# IOT_Masterv1.net
KiCad netlist of a schematic drawn in Altium Designer
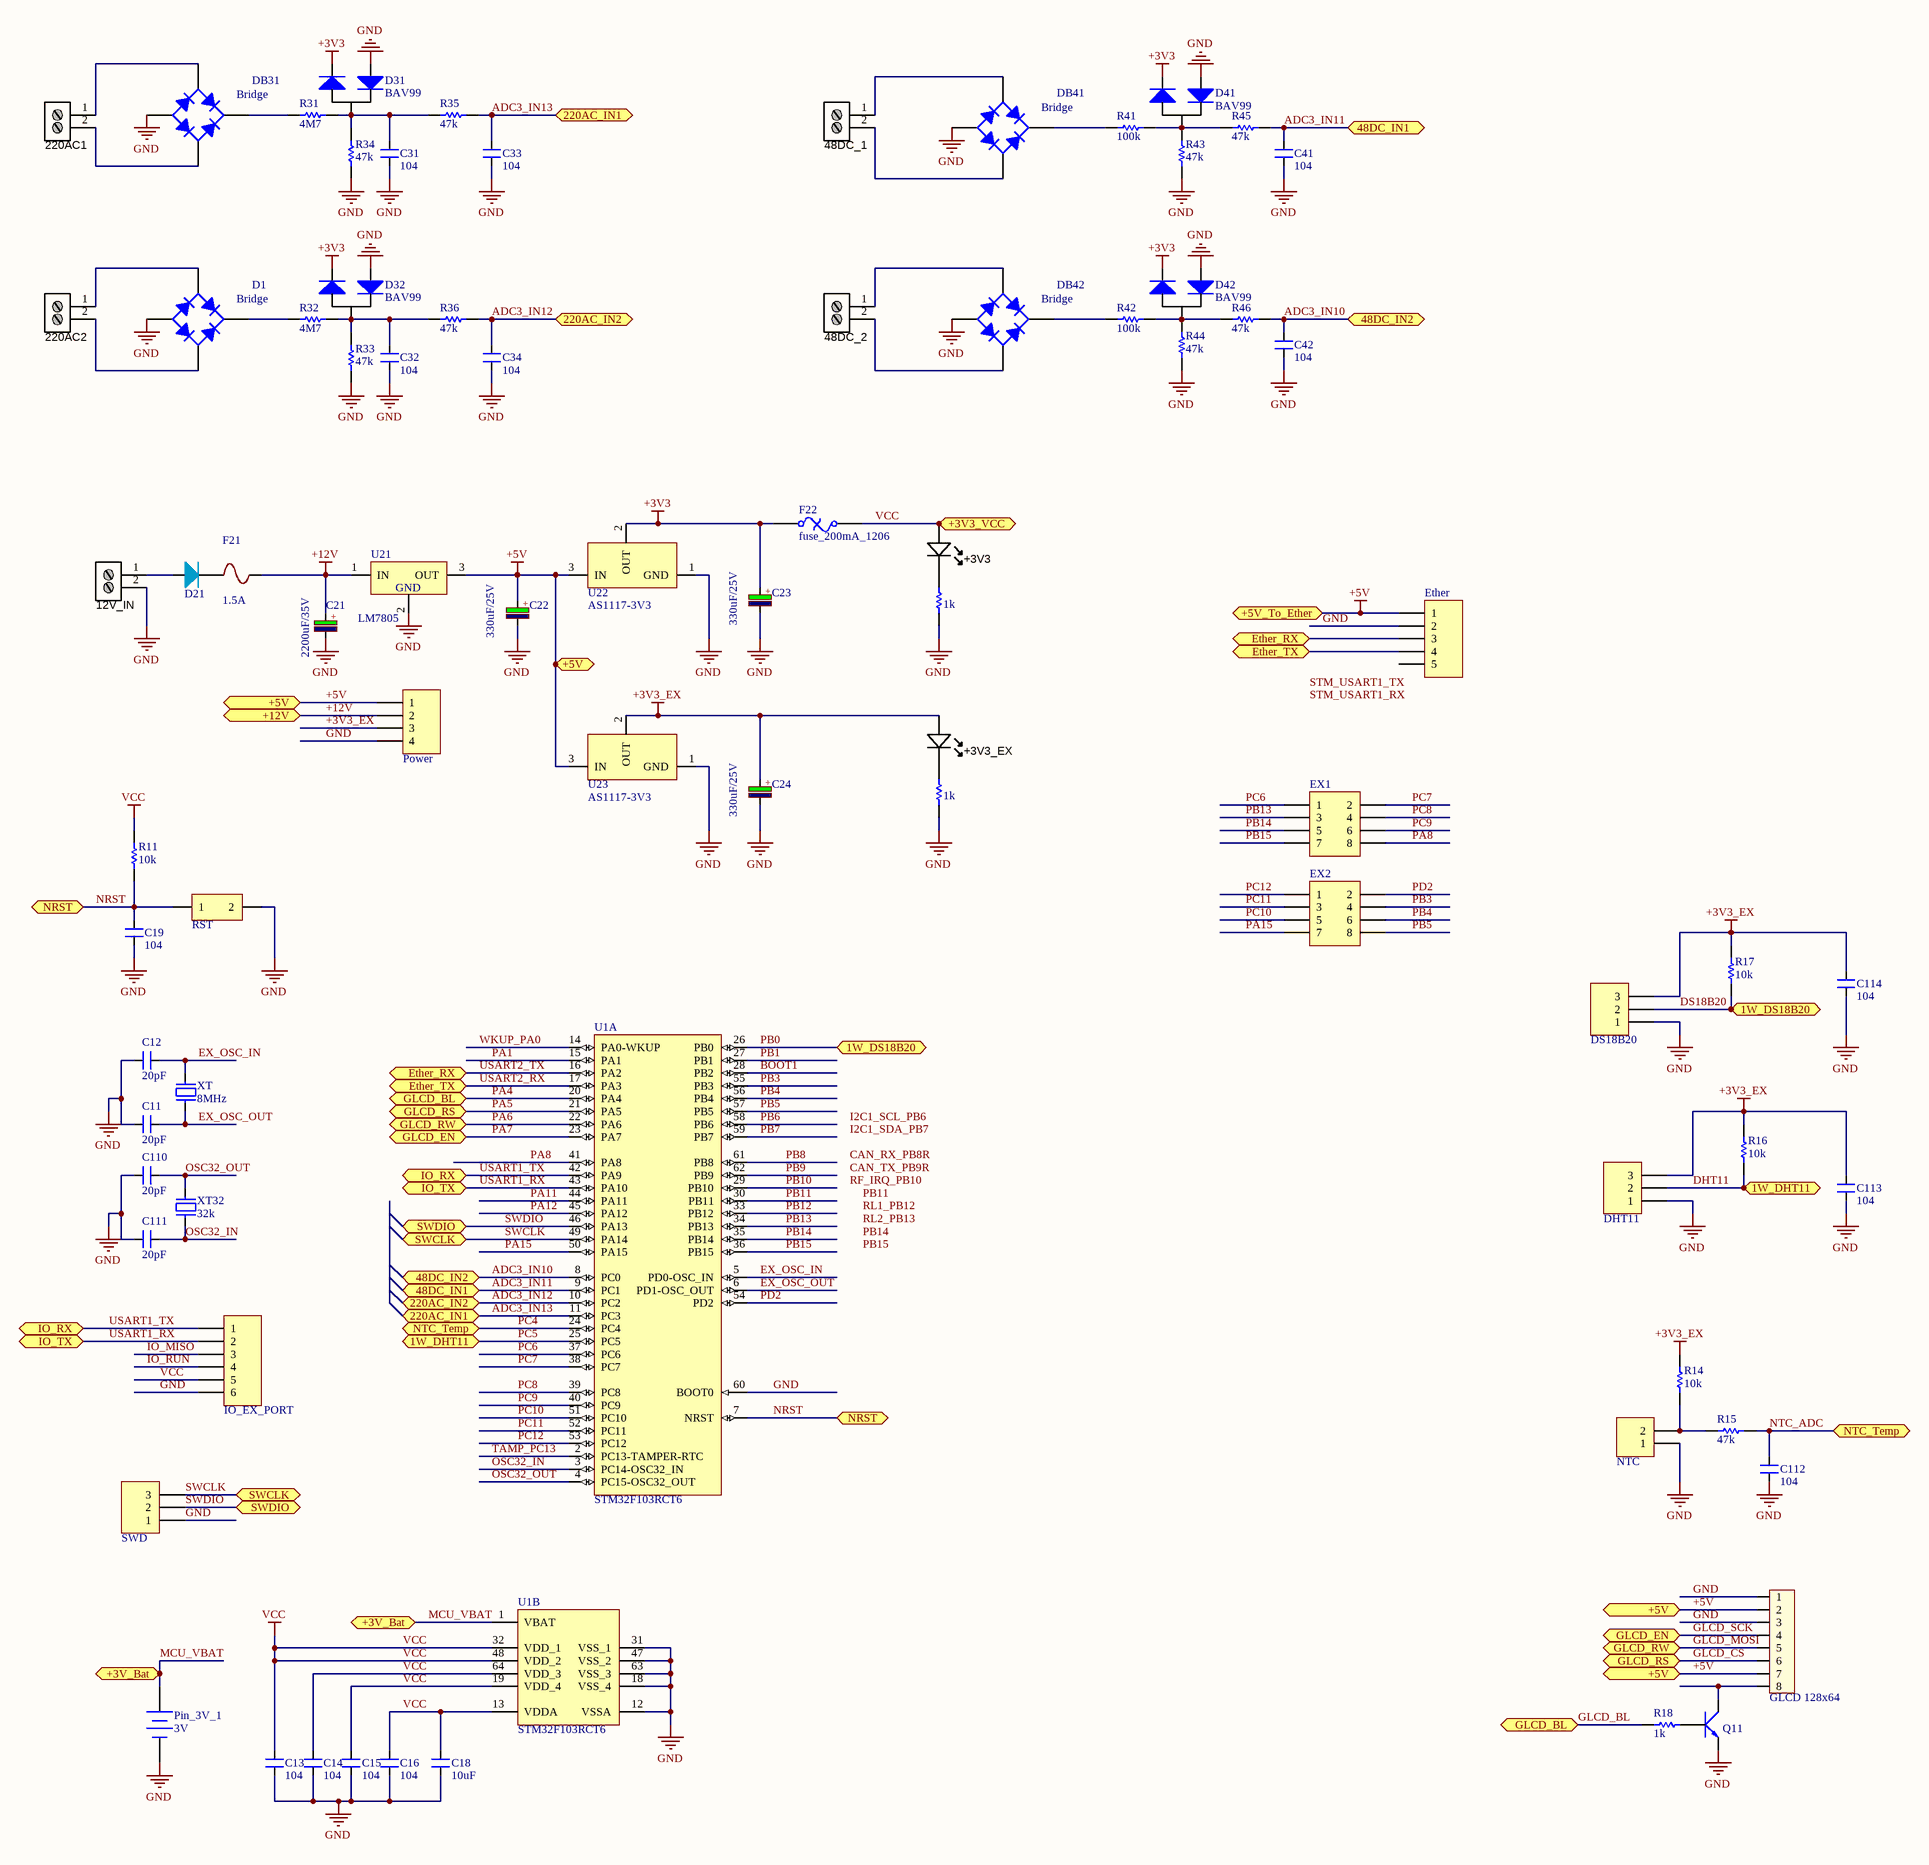
[diagram p0: IOT_Masterv1.SchDoc]

(export (version "E")
  (design (tool "Eeschema 10.0.6"))
  (components
    (comp (ref "+3V3")
      (value "Blue")
      (footprint "LED-0805-K")
      (description "LED 0805 SMD Blue 100mcd 470nm")
      (libsource (lib "PBL - Light Sources") (part "LED_SMD_Blue_0805_100mcd"))
    )
    (comp (ref "+3V3_EX")
      (value "Blue")
      (footprint "LED-0805-K")
      (description "LED 0805 SMD Blue 100mcd 470nm")
      (libsource (lib "PBL - Light Sources") (part "LED_SMD_Blue_0805_100mcd"))
    )
    (comp (ref "12V_IN")
      (value "Stackable ScrewTerm")
      (footprint "2P_PCB_ScrewTerm_200mil")
      (description "Terminal Block Screw Type THT 2-Position 3.81mm pitch")
      (libsource (lib "PBL - Connectors") (part "2P_ScrewTerm_90S_3.81MM"))
    )
    (comp (ref "48DC_1")
      (value "Stackable ScrewTerm")
      (footprint "2P_PCB_ScrewTerm_200mil")
      (description "Terminal Block Screw Type THT 2-Position 3.81mm pitch")
      (libsource (lib "PBL - Connectors") (part "2P_ScrewTerm_90S_3.81MM"))
    )
    (comp (ref "48DC_2")
      (value "Stackable ScrewTerm")
      (footprint "2P_PCB_ScrewTerm_200mil")
      (description "Terminal Block Screw Type THT 2-Position 3.81mm pitch")
      (libsource (lib "PBL - Connectors") (part "2P_ScrewTerm_90S_3.81MM"))
    )
    (comp (ref "220AC1")
      (value "Stackable ScrewTerm")
      (footprint "2P_PCB_ScrewTerm_200mil")
      (description "Terminal Block Screw Type THT 2-Position 3.81mm pitch")
      (libsource (lib "PBL - Connectors") (part "2P_ScrewTerm_90S_3.81MM"))
    )
    (comp (ref "220AC2")
      (value "Stackable ScrewTerm")
      (footprint "2P_PCB_ScrewTerm_200mil")
      (description "Terminal Block Screw Type THT 2-Position 3.81mm pitch")
      (libsource (lib "PBL - Connectors") (part "2P_ScrewTerm_90S_3.81MM"))
    )
    (comp (ref "C11")
      (value "20pF")
      (footprint "CAPC1608N")
      (fields (field (name "Comment") "Cap_22p_0603"))
      (libsource (lib "Tuan") (part "CAP NP"))
    )
    (comp (ref "C12")
      (value "20pF")
      (footprint "CAPC1608N")
      (fields (field (name "Comment") "Cap_22p_0603"))
      (libsource (lib "Tuan") (part "CAP NP"))
    )
    (comp (ref "C13")
      (value "104")
      (footprint "CAPC1608N")
      (fields (field (name "Comment") "Cap_104_0603"))
      (libsource (lib "Tuan") (part "CAP NP"))
    )
    (comp (ref "C14")
      (value "104")
      (footprint "CAPC1608N")
      (fields (field (name "Comment") "Cap_104_0603"))
      (libsource (lib "Tuan") (part "CAP NP"))
    )
    (comp (ref "C15")
      (value "104")
      (footprint "CAPC1608N")
      (fields (field (name "Comment") "Cap_104_0603"))
      (libsource (lib "Tuan") (part "CAP NP"))
    )
    (comp (ref "C16")
      (value "104")
      (footprint "CAPC1608N")
      (fields (field (name "Comment") "Cap_104_0603"))
      (libsource (lib "Tuan") (part "CAP NP"))
    )
    (comp (ref "C18")
      (value "10uF")
      (footprint "CAPC2012N_F")
      (fields (field (name "Comment") "Cap_10uF_0805"))
      (libsource (lib "Tuan") (part "CAP NP"))
    )
    (comp (ref "C19")
      (value "104")
      (footprint "CAPC1608N")
      (fields (field (name "Comment") "Cap_104_0603"))
      (libsource (lib "Tuan") (part "CAP NP"))
    )
    (comp (ref "C21")
      (value "2200uF/35V")
      (footprint "heromap:CP_1000uF_25V")
      (description "Cap 1000uF/16V - 220uF/50V")
      (libsource (lib "heromap") (part "CP4"))
    )
    (comp (ref "C22")
      (value "330uF/25V")
      (footprint "heromap:CP1.5/3.4")
      (description "Cap 1000uF/16V - 220uF/50V")
      (libsource (lib "heromap") (part "CP4"))
    )
    (comp (ref "C23")
      (value "330uF/25V")
      (footprint "heromap:CP1.5/3.4")
      (description "Cap 1000uF/16V - 220uF/50V")
      (libsource (lib "heromap") (part "CP4"))
    )
    (comp (ref "C24")
      (value "330uF/25V")
      (footprint "heromap:CP1.5/3.4")
      (description "Cap 1000uF/16V - 220uF/50V")
      (libsource (lib "heromap") (part "CP4"))
    )
    (comp (ref "C31")
      (value "104")
      (footprint "CAPC2012N_F")
      (fields (field (name "Comment") "CAP NP"))
      (libsource (lib "Tuan") (part "CAP NP"))
    )
    (comp (ref "C32")
      (value "104")
      (footprint "CAPC2012N_F")
      (fields (field (name "Comment") "CAP NP"))
      (libsource (lib "Tuan") (part "CAP NP"))
    )
    (comp (ref "C33")
      (value "104")
      (footprint "CAPC1608N")
      (fields (field (name "Comment") "CAP NP"))
      (libsource (lib "Tuan") (part "CAP NP"))
    )
    (comp (ref "C34")
      (value "104")
      (footprint "CAPC1608N")
      (fields (field (name "Comment") "CAP NP"))
      (libsource (lib "Tuan") (part "CAP NP"))
    )
    (comp (ref "C41")
      (value "104")
      (footprint "CAPC1608N")
      (fields (field (name "Comment") "CAP NP"))
      (libsource (lib "Tuan") (part "CAP NP"))
    )
    (comp (ref "C42")
      (value "104")
      (footprint "CAPC1608N")
      (fields (field (name "Comment") "CAP NP"))
      (libsource (lib "Tuan") (part "CAP NP"))
    )
    (comp (ref "C110")
      (value "20pF")
      (footprint "CAPC1608N")
      (fields (field (name "Comment") "Cap_22p_0603"))
      (libsource (lib "Tuan") (part "CAP NP"))
    )
    (comp (ref "C111")
      (value "20pF")
      (footprint "CAPC1608N")
      (fields (field (name "Comment") "Cap_22p_0603"))
      (libsource (lib "Tuan") (part "CAP NP"))
    )
    (comp (ref "C112")
      (value "104")
      (footprint "CAPC1608N")
      (fields (field (name "Comment") "CAP NP"))
      (libsource (lib "Tuan") (part "CAP NP"))
    )
    (comp (ref "C113")
      (value "104")
      (footprint "CAPC1608N")
      (fields (field (name "Comment") "CAP NP"))
      (libsource (lib "Tuan") (part "CAP NP"))
    )
    (comp (ref "C114")
      (value "104")
      (footprint "CAPC1608N")
      (fields (field (name "Comment") "CAP NP"))
      (libsource (lib "Tuan") (part "CAP NP"))
    )
    (comp (ref "D1")
      (value "Bridge")
      (footprint "MB6S")
      (description "Full Wave Diode Bridge")
      (fields (field (name "PUBLISHER") "Altium Limited"))
      (libsource (lib "Miscellaneous Devices") (part "Bridge1"))
    )
    (comp (ref "D21") (value "Diode") (footprint "DO-214AC") (libsource (lib "Tuan") (part "Diode")))
    (comp (ref "D31") (value "BAV99") (footprint "SOT323") (libsource (lib "Tuan") (part "BAV99W")))
    (comp (ref "D32") (value "BAV99") (footprint "SOT323") (libsource (lib "Tuan") (part "BAV99W")))
    (comp (ref "D41") (value "BAV99") (footprint "SOT323") (libsource (lib "Tuan") (part "BAV99W")))
    (comp (ref "D42") (value "BAV99") (footprint "SOT323") (libsource (lib "Tuan") (part "BAV99W")))
    (comp (ref "DB31")
      (value "Bridge")
      (footprint "MB6S")
      (description "Full Wave Diode Bridge")
      (fields (field (name "PUBLISHER") "Altium Limited"))
      (libsource (lib "Miscellaneous Devices") (part "Bridge1"))
    )
    (comp (ref "DB41")
      (value "Bridge")
      (footprint "MB6S")
      (description "Full Wave Diode Bridge")
      (fields (field (name "PUBLISHER") "Altium Limited"))
      (libsource (lib "Miscellaneous Devices") (part "Bridge1"))
    )
    (comp (ref "DB42")
      (value "Bridge")
      (footprint "MB6S")
      (description "Full Wave Diode Bridge")
      (fields (field (name "PUBLISHER") "Altium Limited"))
      (libsource (lib "Miscellaneous Devices") (part "Bridge1"))
    )
    (comp (ref "DHT11")
      (value "Header 3")
      (footprint "heromap:HDR1X3")
      (description "Header, 3-Pin")
      (fields (field (name "PUBLISHER") "Altium Limited"))
      (libsource (lib "heromap") (part "Header 3"))
    )
    (comp (ref "DS18B20")
      (value "Header 3")
      (footprint "heromap:HDR1X3")
      (description "Header, 3-Pin")
      (fields (field (name "PUBLISHER") "Altium Limited"))
      (libsource (lib "heromap") (part "Header 3"))
    )
    (comp (ref "Ether")
      (value "EX_CON")
      (footprint "HDR1X5H")
      (description "Header, 5-Pin, Right Angle")
      (fields (field (name "PUBLISHER") "Altium Limited"))
      (libsource (lib "Miscellaneous Connectors") (part "Header 5H"))
    )
    (comp (ref "EX1")
      (value "Header 4X2")
      (footprint "heromap:HDR2X4")
      (description "Header, 4-Pin, Dual row")
      (fields (field (name "PUBLISHER") "Altium Limited"))
      (libsource (lib "heromap") (part "Header 4X2"))
    )
    (comp (ref "EX2")
      (value "Header 4X2")
      (footprint "heromap:HDR2X4")
      (description "Header, 4-Pin, Dual row")
      (fields (field (name "PUBLISHER") "Altium Limited"))
      (libsource (lib "heromap") (part "Header 4X2"))
    )
    (comp (ref "F21") (value "1.5A") (footprint "FUSE_SR-5-BK") (libsource (lib "Tuan") (part "Fuse")))
    (comp (ref "F22")
      (value "fuse_200mA_1206")
      (footprint "SMD 1206")
      (description "Thermal Fuse")
      (fields (field (name "PUBLISHER") "Altium Limited"))
      (libsource (lib "Miscellaneous Devices") (part "Fuse Thermal"))
    )
    (comp (ref "GLCD 128x64")
      (value "JP8")
      (footprint "CON8")
      (description "Connector 8")
      (libsource (lib "syhaunguyen") (part "Con8"))
    )
    (comp (ref "IO_EX_PORT")
      (value "Header 6")
      (footprint "heromap:HDR1X6")
      (description "Header, 6-Pin")
      (fields (field (name "PUBLISHER") "Altium Limited"))
      (libsource (lib "heromap") (part "Header 6"))
    )
    (comp (ref "NTC")
      (value "NTC_10K")
      (footprint "heromap:HDR1X2")
      (description "Header, 2-Pin")
      (fields (field (name "PUBLISHER") "Altium Limited"))
      (libsource (lib "heromap") (part "Header 2"))
    )
    (comp (ref "Pin_3V_1")
      (value "3V")
      (footprint "CR1220")
      (description "Multicell Battery")
      (fields (field (name "PUBLISHER") "Altium Limited"))
      (libsource (lib "heromap") (part "Battery"))
    )
    (comp (ref "Power")
      (value "Header 4")
      (footprint "heromap:HDR1X4")
      (description "Header, 4-Pin")
      (fields (field (name "PUBLISHER") "Altium Limited"))
      (libsource (lib "heromap") (part "Header 4"))
    )
    (comp (ref "Q11")
      (value "C828")
      (footprint "SOT23 TOP")
      (description "Transistor C828 C1815....")
      (libsource (lib "Tuan") (part "NPN"))
    )
    (comp (ref "R11")
      (value "10k")
      (footprint "RESC1608N_F")
      (fields (field (name "Comment") "Res_10k_0603"))
      (libsource (lib "Tuan") (part "Res"))
    )
    (comp (ref "R14")
      (value "10k")
      (footprint "RESC1608N_ZERO")
      (fields (field (name "Comment") "Res"))
      (libsource (lib "Tuan") (part "Res"))
    )
    (comp (ref "R15")
      (value "47k")
      (footprint "RESC2012N_F")
      (fields (field (name "Comment") "Res"))
      (libsource (lib "Tuan") (part "Res"))
    )
    (comp (ref "R16")
      (value "10k")
      (footprint "RESC1608N_ZERO")
      (fields (field (name "Comment") "Res"))
      (libsource (lib "Tuan") (part "Res"))
    )
    (comp (ref "R17")
      (value "10k")
      (footprint "RESC1608N_ZERO")
      (fields (field (name "Comment") "Res"))
      (libsource (lib "Tuan") (part "Res"))
    )
    (comp (ref "R18")
      (value "1k")
      (footprint "RESC1608N_ZERO")
      (fields (field (name "Comment") "Res"))
      (libsource (lib "Tuan") (part "Res"))
    )
    (comp (ref "R21")
      (value "1k")
      (footprint "RESC2012N_F")
      (fields (field (name "Comment") "Res_0805_1k"))
      (libsource (lib "Tuan") (part "Res"))
    )
    (comp (ref "R22")
      (value "1k")
      (footprint "RESC2012N_F")
      (fields (field (name "Comment") "Res_0805_1k"))
      (libsource (lib "Tuan") (part "Res"))
    )
    (comp (ref "R31")
      (value "4M7")
      (footprint "RESTH_0.0R_AXIAL-0.6")
      (fields (field (name "Comment") "Res"))
      (libsource (lib "Tuan") (part "Res"))
    )
    (comp (ref "R32")
      (value "4M7")
      (footprint "RESTH_0.0R_AXIAL-0.6")
      (fields (field (name "Comment") "Res"))
      (libsource (lib "Tuan") (part "Res"))
    )
    (comp (ref "R33")
      (value "47k")
      (footprint "RESTH_0.0R_AXIAL-0.6")
      (fields (field (name "Comment") "Res"))
      (libsource (lib "Tuan") (part "Res"))
    )
    (comp (ref "R34")
      (value "47k")
      (footprint "RESTH_0.0R_AXIAL-0.6")
      (fields (field (name "Comment") "Res"))
      (libsource (lib "Tuan") (part "Res"))
    )
    (comp (ref "R35")
      (value "47k")
      (footprint "RESC2012N_F")
      (fields (field (name "Comment") "Res"))
      (libsource (lib "Tuan") (part "Res"))
    )
    (comp (ref "R36")
      (value "47k")
      (footprint "RESC2012N_F")
      (fields (field (name "Comment") "Res"))
      (libsource (lib "Tuan") (part "Res"))
    )
    (comp (ref "R41")
      (value "100k")
      (footprint "RESTH_0.0R_AXIAL-0.6")
      (fields (field (name "Comment") "Res"))
      (libsource (lib "Tuan") (part "Res"))
    )
    (comp (ref "R42")
      (value "100k")
      (footprint "RESTH_0.0R_AXIAL-0.6")
      (fields (field (name "Comment") "Res"))
      (libsource (lib "Tuan") (part "Res"))
    )
    (comp (ref "R43")
      (value "47k")
      (footprint "RESTH_0.0R_AXIAL-0.6")
      (fields (field (name "Comment") "Res"))
      (libsource (lib "Tuan") (part "Res"))
    )
    (comp (ref "R44")
      (value "47k")
      (footprint "RESTH_0.0R_AXIAL-0.6")
      (fields (field (name "Comment") "Res"))
      (libsource (lib "Tuan") (part "Res"))
    )
    (comp (ref "R45")
      (value "47k")
      (footprint "RESC2012N_F")
      (fields (field (name "Comment") "Res"))
      (libsource (lib "Tuan") (part "Res"))
    )
    (comp (ref "R46")
      (value "47k")
      (footprint "RESC2012N_F")
      (fields (field (name "Comment") "Res"))
      (libsource (lib "Tuan") (part "Res"))
    )
    (comp (ref "RST") (value "Button") (footprint "SW") (libsource (lib "Tuan") (part "Button I")))
    (comp (ref "SWD")
      (value "Header 3")
      (footprint "heromap:HDR1X3")
      (description "Header, 3-Pin")
      (fields (field (name "PUBLISHER") "Altium Limited"))
      (libsource (lib "heromap") (part "Header 3"))
    )
    (comp (ref "U1")
      (value "STM32F103RCT6")
      (footprint "STM-LQFP64_N")
      (libsource (lib "STMicroelectronics STM32 F1") (part "STM32F103RCT6"))
    )
    (comp (ref "U21") (value "LM7805") (footprint "TO-220") (libsource (lib "Tuan") (part "LM78xx")))
    (comp (ref "U22") (value "AS1117-3V3") (footprint "SOT223-4N") (libsource (lib "Tuan") (part "AS1117")))
    (comp (ref "U23") (value "AS1117-3V3") (footprint "SOT223-4N") (libsource (lib "Tuan") (part "AS1117")))
    (comp (ref "XT") (value "8MHz") (footprint "XT2") (libsource (lib "Tuan") (part "Crystal")))
    (comp (ref "XT32") (value "32k") (footprint "XTminiv2") (libsource (lib "Tuan") (part "Crystal")))
  )
  (nets
    (net (code "1") (name "+3V3") (class "Default")
      (node (ref "C23") (pin "1") (pinfunction "1_1") (pintype "passive"))
      (node (ref "D31") (pin "2") (pinfunction "K_2") (pintype "passive"))
      (node (ref "D32") (pin "2") (pinfunction "K_2") (pintype "passive"))
      (node (ref "D41") (pin "2") (pinfunction "K_2") (pintype "passive"))
      (node (ref "D42") (pin "2") (pinfunction "K_2") (pintype "passive"))
      (node (ref "F22") (pin "1") (pinfunction "1_1") (pintype "passive"))
      (node (ref "U22") (pin "2") (pinfunction "OUT_2") (pintype "power_in"))
    )
    (net (code "2") (name "+3V3_EX") (class "Default")
      (node (ref "+3V3_EX") (pin "A") (pinfunction "A_A") (pintype "passive"))
      (node (ref "C113") (pin "2") (pinfunction "2_2") (pintype "passive"))
      (node (ref "C114") (pin "2") (pinfunction "2_2") (pintype "passive"))
      (node (ref "C24") (pin "1") (pinfunction "1_1") (pintype "passive"))
      (node (ref "DHT11") (pin "3") (pinfunction "3_3") (pintype "passive"))
      (node (ref "DS18B20") (pin "3") (pinfunction "3_3") (pintype "passive"))
      (node (ref "Power") (pin "3") (pinfunction "3_3") (pintype "passive"))
      (node (ref "R14") (pin "2") (pinfunction "2_2") (pintype "passive"))
      (node (ref "R16") (pin "2") (pinfunction "2_2") (pintype "passive"))
      (node (ref "R17") (pin "2") (pinfunction "2_2") (pintype "passive"))
      (node (ref "U23") (pin "2") (pinfunction "OUT_2") (pintype "power_in"))
    )
    (net (code "3") (name "+5V") (class "Default")
      (node (ref "C22") (pin "1") (pinfunction "1_1") (pintype "passive"))
      (node (ref "Ether") (pin "1") (pinfunction "1_1") (pintype "passive"))
      (node (ref "GLCD 128x64") (pin "2") (pinfunction "2_2") (pintype "passive"))
      (node (ref "GLCD 128x64") (pin "7") (pinfunction "7_7") (pintype "passive"))
      (node (ref "Power") (pin "1") (pinfunction "1_1") (pintype "passive"))
      (node (ref "U21") (pin "3") (pinfunction "OUT_3") (pintype "passive"))
      (node (ref "U22") (pin "3") (pinfunction "IN_3") (pintype "power_in"))
      (node (ref "U23") (pin "3") (pinfunction "IN_3") (pintype "power_in"))
    )
    (net (code "4") (name "+12V") (class "Default")
      (node (ref "C21") (pin "1") (pinfunction "1_1") (pintype "passive"))
      (node (ref "F21") (pin "2") (pinfunction "2_2") (pintype "passive"))
      (node (ref "Power") (pin "2") (pinfunction "2_2") (pintype "passive"))
      (node (ref "U21") (pin "1") (pinfunction "IN_1") (pintype "passive"))
    )
    (net (code "5") (name "/ADC3_IN10") (class "Default")
      (node (ref "C42") (pin "2") (pinfunction "2_2") (pintype "passive"))
      (node (ref "R46") (pin "2") (pinfunction "2_2") (pintype "passive"))
      (node (ref "U1") (pin "8") (pinfunction "PC0_8") (pintype "bidirectional"))
    )
    (net (code "6") (name "/ADC3_IN11") (class "Default")
      (node (ref "C41") (pin "2") (pinfunction "2_2") (pintype "passive"))
      (node (ref "R45") (pin "2") (pinfunction "2_2") (pintype "passive"))
      (node (ref "U1") (pin "9") (pinfunction "PC1_9") (pintype "bidirectional"))
    )
    (net (code "7") (name "/ADC3_IN12") (class "Default")
      (node (ref "C34") (pin "2") (pinfunction "2_2") (pintype "passive"))
      (node (ref "R36") (pin "2") (pinfunction "2_2") (pintype "passive"))
      (node (ref "U1") (pin "10") (pinfunction "PC2_10") (pintype "bidirectional"))
    )
    (net (code "8") (name "/ADC3_IN13") (class "Default")
      (node (ref "C33") (pin "2") (pinfunction "2_2") (pintype "passive"))
      (node (ref "R35") (pin "2") (pinfunction "2_2") (pintype "passive"))
      (node (ref "U1") (pin "11") (pinfunction "PC3_11") (pintype "bidirectional"))
    )
    (net (code "9") (name "/BOOT1") (class "Default")
      (node (ref "U1") (pin "28") (pinfunction "PB2_28") (pintype "bidirectional"))
    )
    (net (code "12") (name "/DHT11") (class "Default")
      (node (ref "DHT11") (pin "2") (pinfunction "2_2") (pintype "passive"))
      (node (ref "R16") (pin "1") (pinfunction "1_1") (pintype "passive"))
      (node (ref "U1") (pin "25") (pinfunction "PC5_25") (pintype "bidirectional"))
    )
    (net (code "13") (name "/DS18B20") (class "Default")
      (node (ref "DS18B20") (pin "2") (pinfunction "2_2") (pintype "passive"))
      (node (ref "R17") (pin "1") (pinfunction "1_1") (pintype "passive"))
      (node (ref "U1") (pin "26") (pinfunction "PB0_26") (pintype "bidirectional"))
    )
    (net (code "14") (name "/EX_OSC_IN") (class "Default")
      (node (ref "C12") (pin "1") (pinfunction "1_1") (pintype "passive"))
      (node (ref "U1") (pin "5") (pinfunction "PD0-OSC_IN_5") (pintype "bidirectional"))
      (node (ref "XT") (pin "2") (pinfunction "2_2") (pintype "passive"))
    )
    (net (code "15") (name "/EX_OSC_OUT") (class "Default")
      (node (ref "C11") (pin "1") (pinfunction "1_1") (pintype "passive"))
      (node (ref "U1") (pin "6") (pinfunction "PD1-OSC_OUT_6") (pintype "bidirectional"))
      (node (ref "XT") (pin "1") (pinfunction "1_1") (pintype "passive"))
    )
    (net (code "16") (name "/GLCD_BL") (class "Default")
      (node (ref "R18") (pin "1") (pinfunction "1_1") (pintype "passive"))
      (node (ref "U1") (pin "20") (pinfunction "PA4_20") (pintype "bidirectional"))
    )
    (net (code "17") (name "/GLCD_CS") (class "Default")
      (node (ref "GLCD 128x64") (pin "6") (pinfunction "6_6") (pintype "passive"))
      (node (ref "U1") (pin "21") (pinfunction "PA5_21") (pintype "bidirectional"))
    )
    (net (code "18") (name "/GLCD_MOSI") (class "Default")
      (node (ref "GLCD 128x64") (pin "5") (pinfunction "5_5") (pintype "passive"))
      (node (ref "U1") (pin "22") (pinfunction "PA6_22") (pintype "bidirectional"))
    )
    (net (code "19") (name "/GLCD_SCK") (class "Default")
      (node (ref "GLCD 128x64") (pin "4") (pinfunction "4_4") (pintype "passive"))
      (node (ref "U1") (pin "23") (pinfunction "PA7_23") (pintype "bidirectional"))
    )
    (net (code "22") (name "/IO_MISO") (class "Default")
      (node (ref "IO_EX_PORT") (pin "3") (pinfunction "3_3") (pintype "passive"))
    )
    (net (code "23") (name "/IO_RUN") (class "Default")
      (node (ref "IO_EX_PORT") (pin "4") (pinfunction "4_4") (pintype "passive"))
    )
    (net (code "24") (name "/MCU_VBAT") (class "Default")
      (node (ref "Pin_3V_1") (pin "1") (pinfunction "+_1") (pintype "passive"))
      (node (ref "U1") (pin "1") (pinfunction "VBAT_1") (pintype "power_in"))
    )
    (net (code "25") (name "/NRST") (class "Default")
      (node (ref "C19") (pin "2") (pinfunction "2_2") (pintype "passive"))
      (node (ref "R11") (pin "1") (pinfunction "1_1") (pintype "passive"))
      (node (ref "RST") (pin "1") (pinfunction "1_1") (pintype "power_in"))
      (node (ref "U1") (pin "7") (pinfunction "NRST_7") (pintype "bidirectional"))
    )
    (net (code "26") (name "/NTC_ADC") (class "Default")
      (node (ref "C112") (pin "2") (pinfunction "2_2") (pintype "passive"))
      (node (ref "R15") (pin "2") (pinfunction "2_2") (pintype "passive"))
      (node (ref "U1") (pin "24") (pinfunction "PC4_24") (pintype "bidirectional"))
    )
    (net (code "27") (name "/OSC32_IN") (class "Default")
      (node (ref "C111") (pin "1") (pinfunction "1_1") (pintype "passive"))
      (node (ref "U1") (pin "3") (pinfunction "PC14-OSC32_IN_3") (pintype "bidirectional"))
      (node (ref "XT32") (pin "1") (pinfunction "1_1") (pintype "passive"))
    )
    (net (code "28") (name "/OSC32_OUT") (class "Default")
      (node (ref "C110") (pin "1") (pinfunction "1_1") (pintype "passive"))
      (node (ref "U1") (pin "4") (pinfunction "PC15-OSC32_OUT_4") (pintype "bidirectional"))
      (node (ref "XT32") (pin "2") (pinfunction "2_2") (pintype "passive"))
    )
    (net (code "29") (name "/PA1") (class "Default")
      (node (ref "U1") (pin "15") (pinfunction "PA1_15") (pintype "bidirectional"))
    )
    (net (code "30") (name "/PA8") (class "Default")
      (node (ref "EX1") (pin "8") (pinfunction "8_8") (pintype "passive"))
      (node (ref "U1") (pin "41") (pinfunction "PA8_41") (pintype "bidirectional"))
    )
    (net (code "31") (name "/PA11") (class "Default")
      (node (ref "U1") (pin "44") (pinfunction "PA11_44") (pintype "bidirectional"))
    )
    (net (code "32") (name "/PA12") (class "Default")
      (node (ref "U1") (pin "45") (pinfunction "PA12_45") (pintype "bidirectional"))
    )
    (net (code "33") (name "/PA15") (class "Default")
      (node (ref "EX2") (pin "7") (pinfunction "7_7") (pintype "passive"))
      (node (ref "U1") (pin "50") (pinfunction "PA15_50") (pintype "bidirectional"))
    )
    (net (code "34") (name "/PB1") (class "Default")
      (node (ref "U1") (pin "27") (pinfunction "PB1_27") (pintype "bidirectional"))
    )
    (net (code "35") (name "/PB3") (class "Default")
      (node (ref "EX2") (pin "4") (pinfunction "4_4") (pintype "passive"))
      (node (ref "U1") (pin "55") (pinfunction "PB3_55") (pintype "bidirectional"))
    )
    (net (code "36") (name "/PB4") (class "Default")
      (node (ref "EX2") (pin "6") (pinfunction "6_6") (pintype "passive"))
      (node (ref "U1") (pin "56") (pinfunction "PB4_56") (pintype "bidirectional"))
    )
    (net (code "37") (name "/PB5") (class "Default")
      (node (ref "EX2") (pin "8") (pinfunction "8_8") (pintype "passive"))
      (node (ref "U1") (pin "57") (pinfunction "PB5_57") (pintype "bidirectional"))
    )
    (net (code "38") (name "/PB6") (class "Default")
      (node (ref "U1") (pin "58") (pinfunction "PB6_58") (pintype "bidirectional"))
    )
    (net (code "39") (name "/PB7") (class "Default")
      (node (ref "U1") (pin "59") (pinfunction "PB7_59") (pintype "bidirectional"))
    )
    (net (code "40") (name "/PB8") (class "Default")
      (node (ref "U1") (pin "61") (pinfunction "PB8_61") (pintype "bidirectional"))
    )
    (net (code "41") (name "/PB9") (class "Default")
      (node (ref "U1") (pin "62") (pinfunction "PB9_62") (pintype "bidirectional"))
    )
    (net (code "42") (name "/PB10") (class "Default")
      (node (ref "U1") (pin "29") (pinfunction "PB10_29") (pintype "bidirectional"))
    )
    (net (code "43") (name "/PB11") (class "Default")
      (node (ref "U1") (pin "30") (pinfunction "PB11_30") (pintype "bidirectional"))
    )
    (net (code "44") (name "/PB12") (class "Default")
      (node (ref "U1") (pin "33") (pinfunction "PB12_33") (pintype "bidirectional"))
    )
    (net (code "45") (name "/PB13") (class "Default")
      (node (ref "EX1") (pin "3") (pinfunction "3_3") (pintype "passive"))
      (node (ref "U1") (pin "34") (pinfunction "PB13_34") (pintype "bidirectional"))
    )
    (net (code "46") (name "/PB14") (class "Default")
      (node (ref "EX1") (pin "5") (pinfunction "5_5") (pintype "passive"))
      (node (ref "U1") (pin "35") (pinfunction "PB14_35") (pintype "bidirectional"))
    )
    (net (code "47") (name "/PB15") (class "Default")
      (node (ref "EX1") (pin "7") (pinfunction "7_7") (pintype "passive"))
      (node (ref "U1") (pin "36") (pinfunction "PB15_36") (pintype "bidirectional"))
    )
    (net (code "48") (name "/PC6") (class "Default")
      (node (ref "EX1") (pin "1") (pinfunction "1_1") (pintype "passive"))
      (node (ref "U1") (pin "37") (pinfunction "PC6_37") (pintype "bidirectional"))
    )
    (net (code "49") (name "/PC7") (class "Default")
      (node (ref "EX1") (pin "2") (pinfunction "2_2") (pintype "passive"))
      (node (ref "U1") (pin "38") (pinfunction "PC7_38") (pintype "bidirectional"))
    )
    (net (code "50") (name "/PC8") (class "Default")
      (node (ref "EX1") (pin "4") (pinfunction "4_4") (pintype "passive"))
      (node (ref "U1") (pin "39") (pinfunction "PC8_39") (pintype "bidirectional"))
    )
    (net (code "51") (name "/PC9") (class "Default")
      (node (ref "EX1") (pin "6") (pinfunction "6_6") (pintype "passive"))
      (node (ref "U1") (pin "40") (pinfunction "PC9_40") (pintype "bidirectional"))
    )
    (net (code "52") (name "/PC10") (class "Default")
      (node (ref "EX2") (pin "5") (pinfunction "5_5") (pintype "passive"))
      (node (ref "U1") (pin "51") (pinfunction "PC10_51") (pintype "bidirectional"))
    )
    (net (code "53") (name "/PC11") (class "Default")
      (node (ref "EX2") (pin "3") (pinfunction "3_3") (pintype "passive"))
      (node (ref "U1") (pin "52") (pinfunction "PC11_52") (pintype "bidirectional"))
    )
    (net (code "54") (name "/PC12") (class "Default")
      (node (ref "EX2") (pin "1") (pinfunction "1_1") (pintype "passive"))
      (node (ref "U1") (pin "53") (pinfunction "PC12_53") (pintype "bidirectional"))
    )
    (net (code "55") (name "/PD2") (class "Default")
      (node (ref "EX2") (pin "2") (pinfunction "2_2") (pintype "passive"))
      (node (ref "U1") (pin "54") (pinfunction "PD2_54") (pintype "bidirectional"))
    )
    (net (code "61") (name "/SWCLK") (class "Default")
      (node (ref "SWD") (pin "3") (pinfunction "3_3") (pintype "passive"))
      (node (ref "U1") (pin "49") (pinfunction "PA14_49") (pintype "bidirectional"))
    )
    (net (code "62") (name "/SWDIO") (class "Default")
      (node (ref "SWD") (pin "2") (pinfunction "2_2") (pintype "passive"))
      (node (ref "U1") (pin "46") (pinfunction "PA13_46") (pintype "bidirectional"))
    )
    (net (code "63") (name "/TAMP_PC13") (class "Default")
      (node (ref "U1") (pin "2") (pinfunction "PC13-TAMPER-RTC_2") (pintype "bidirectional"))
    )
    (net (code "64") (name "/USART1_RX") (class "Default")
      (node (ref "IO_EX_PORT") (pin "2") (pinfunction "2_2") (pintype "passive"))
      (node (ref "U1") (pin "43") (pinfunction "PA10_43") (pintype "bidirectional"))
    )
    (net (code "65") (name "/USART1_TX") (class "Default")
      (node (ref "IO_EX_PORT") (pin "1") (pinfunction "1_1") (pintype "passive"))
      (node (ref "U1") (pin "42") (pinfunction "PA9_42") (pintype "bidirectional"))
    )
    (net (code "66") (name "/USART2_RX") (class "Default")
      (node (ref "Ether") (pin "4") (pinfunction "4_4") (pintype "passive"))
      (node (ref "U1") (pin "17") (pinfunction "PA3_17") (pintype "bidirectional"))
    )
    (net (code "67") (name "/USART2_TX") (class "Default")
      (node (ref "Ether") (pin "3") (pinfunction "3_3") (pintype "passive"))
      (node (ref "U1") (pin "16") (pinfunction "PA2_16") (pintype "bidirectional"))
    )
    (net (code "68") (name "/WKUP_PA0") (class "Default")
      (node (ref "U1") (pin "14") (pinfunction "PA0-WKUP_14") (pintype "bidirectional"))
    )
    (net (code "69") (name "GND") (class "Default")
      (node (ref "12V_IN") (pin "2") (pinfunction "2_2") (pintype "passive"))
      (node (ref "C11") (pin "2") (pinfunction "2_2") (pintype "passive"))
      (node (ref "C110") (pin "2") (pinfunction "2_2") (pintype "passive"))
      (node (ref "C111") (pin "2") (pinfunction "2_2") (pintype "passive"))
      (node (ref "C112") (pin "1") (pinfunction "1_1") (pintype "passive"))
      (node (ref "C113") (pin "1") (pinfunction "1_1") (pintype "passive"))
      (node (ref "C114") (pin "1") (pinfunction "1_1") (pintype "passive"))
      (node (ref "C12") (pin "2") (pinfunction "2_2") (pintype "passive"))
      (node (ref "C13") (pin "1") (pinfunction "1_1") (pintype "passive"))
      (node (ref "C14") (pin "1") (pinfunction "1_1") (pintype "passive"))
      (node (ref "C15") (pin "1") (pinfunction "1_1") (pintype "passive"))
      (node (ref "C16") (pin "1") (pinfunction "1_1") (pintype "passive"))
      (node (ref "C18") (pin "1") (pinfunction "1_1") (pintype "passive"))
      (node (ref "C19") (pin "1") (pinfunction "1_1") (pintype "passive"))
      (node (ref "C21") (pin "2") (pinfunction "2_2") (pintype "passive"))
      (node (ref "C22") (pin "2") (pinfunction "2_2") (pintype "passive"))
      (node (ref "C23") (pin "2") (pinfunction "2_2") (pintype "passive"))
      (node (ref "C24") (pin "2") (pinfunction "2_2") (pintype "passive"))
      (node (ref "C31") (pin "1") (pinfunction "1_1") (pintype "passive"))
      (node (ref "C32") (pin "1") (pinfunction "1_1") (pintype "passive"))
      (node (ref "C33") (pin "1") (pinfunction "1_1") (pintype "passive"))
      (node (ref "C34") (pin "1") (pinfunction "1_1") (pintype "passive"))
      (node (ref "C41") (pin "1") (pinfunction "1_1") (pintype "passive"))
      (node (ref "C42") (pin "1") (pinfunction "1_1") (pintype "passive"))
      (node (ref "D1") (pin "3") (pinfunction "A_3") (pintype "passive"))
      (node (ref "D31") (pin "1") (pinfunction "A_1") (pintype "passive"))
      (node (ref "D32") (pin "1") (pinfunction "A_1") (pintype "passive"))
      (node (ref "D41") (pin "1") (pinfunction "A_1") (pintype "passive"))
      (node (ref "D42") (pin "1") (pinfunction "A_1") (pintype "passive"))
      (node (ref "DB31") (pin "3") (pinfunction "A_3") (pintype "passive"))
      (node (ref "DB41") (pin "3") (pinfunction "A_3") (pintype "passive"))
      (node (ref "DB42") (pin "3") (pinfunction "A_3") (pintype "passive"))
      (node (ref "DHT11") (pin "1") (pinfunction "1_1") (pintype "passive"))
      (node (ref "DS18B20") (pin "1") (pinfunction "1_1") (pintype "passive"))
      (node (ref "Ether") (pin "2") (pinfunction "2_2") (pintype "passive"))
      (node (ref "GLCD 128x64") (pin "1") (pinfunction "1_1") (pintype "passive"))
      (node (ref "GLCD 128x64") (pin "3") (pinfunction "3_3") (pintype "passive"))
      (node (ref "IO_EX_PORT") (pin "6") (pinfunction "6_6") (pintype "passive"))
      (node (ref "NTC") (pin "1") (pinfunction "1_1") (pintype "passive"))
      (node (ref "Pin_3V_1") (pin "2") (pinfunction "-_2") (pintype "passive"))
      (node (ref "Power") (pin "4") (pinfunction "4_4") (pintype "passive"))
      (node (ref "Q11") (pin "3") (pinfunction "E_3") (pintype "passive"))
      (node (ref "R21") (pin "2") (pinfunction "2_2") (pintype "passive"))
      (node (ref "R22") (pin "2") (pinfunction "2_2") (pintype "passive"))
      (node (ref "R33") (pin "1") (pinfunction "1_1") (pintype "passive"))
      (node (ref "R34") (pin "1") (pinfunction "1_1") (pintype "passive"))
      (node (ref "R43") (pin "1") (pinfunction "1_1") (pintype "passive"))
      (node (ref "R44") (pin "1") (pinfunction "1_1") (pintype "passive"))
      (node (ref "RST") (pin "2") (pinfunction "2_2") (pintype "power_in"))
      (node (ref "SWD") (pin "1") (pinfunction "1_1") (pintype "passive"))
      (node (ref "U1") (pin "12") (pinfunction "VSSA_12") (pintype "power_in"))
      (node (ref "U1") (pin "18") (pinfunction "VSS_4_18") (pintype "power_in"))
      (node (ref "U1") (pin "31") (pinfunction "VSS_1_31") (pintype "power_in"))
      (node (ref "U1") (pin "47") (pinfunction "VSS_2_47") (pintype "power_in"))
      (node (ref "U1") (pin "60") (pinfunction "BOOT0_60") (pintype "input"))
      (node (ref "U1") (pin "63") (pinfunction "VSS_3_63") (pintype "power_in"))
      (node (ref "U21") (pin "2") (pintype "passive"))
      (node (ref "U22") (pin "1") (pinfunction "GND_1") (pintype "power_in"))
      (node (ref "U23") (pin "1") (pinfunction "GND_1") (pintype "power_in"))
    )
    (net (code "70") (name "Net-(+3V3-PadK)") (class "Default")
      (node (ref "+3V3") (pin "K") (pinfunction "K_K") (pintype "passive"))
      (node (ref "R21") (pin "1") (pinfunction "1_1") (pintype "passive"))
    )
    (net (code "71") (name "Net-(+3V3_EX-PadK)") (class "Default")
      (node (ref "+3V3_EX") (pin "K") (pinfunction "K_K") (pintype "passive"))
      (node (ref "R22") (pin "1") (pinfunction "1_1") (pintype "passive"))
    )
    (net (code "72") (name "Net-(48DC_1-Pad1)") (class "Default")
      (node (ref "48DC_1") (pin "1") (pinfunction "1_1") (pintype "passive"))
      (node (ref "DB41") (pin "4") (pinfunction "C_4") (pintype "passive"))
    )
    (net (code "73") (name "Net-(48DC_1-Pad2)") (class "Default")
      (node (ref "48DC_1") (pin "2") (pinfunction "2_2") (pintype "passive"))
      (node (ref "DB41") (pin "2") (pinfunction "C_2") (pintype "passive"))
    )
    (net (code "74") (name "Net-(48DC_2-Pad1)") (class "Default")
      (node (ref "48DC_2") (pin "1") (pinfunction "1_1") (pintype "passive"))
      (node (ref "DB42") (pin "4") (pinfunction "C_4") (pintype "passive"))
    )
    (net (code "75") (name "Net-(48DC_2-Pad2)") (class "Default")
      (node (ref "48DC_2") (pin "2") (pinfunction "2_2") (pintype "passive"))
      (node (ref "DB42") (pin "2") (pinfunction "C_2") (pintype "passive"))
    )
    (net (code "76") (name "Net-(220AC1-Pad1)") (class "Default")
      (node (ref "220AC1") (pin "1") (pinfunction "1_1") (pintype "passive"))
      (node (ref "DB31") (pin "4") (pinfunction "C_4") (pintype "passive"))
    )
    (net (code "77") (name "Net-(220AC1-Pad2)") (class "Default")
      (node (ref "220AC1") (pin "2") (pinfunction "2_2") (pintype "passive"))
      (node (ref "DB31") (pin "2") (pinfunction "C_2") (pintype "passive"))
    )
    (net (code "78") (name "Net-(220AC2-Pad1)") (class "Default")
      (node (ref "220AC2") (pin "1") (pinfunction "1_1") (pintype "passive"))
      (node (ref "D1") (pin "4") (pinfunction "C_4") (pintype "passive"))
    )
    (net (code "79") (name "Net-(220AC2-Pad2)") (class "Default")
      (node (ref "220AC2") (pin "2") (pinfunction "2_2") (pintype "passive"))
      (node (ref "D1") (pin "2") (pinfunction "C_2") (pintype "passive"))
    )
    (net (code "80") (name "Net-(D1-K)") (class "Default")
      (node (ref "D1") (pin "1") (pinfunction "K_1") (pintype "passive"))
      (node (ref "R32") (pin "1") (pinfunction "1_1") (pintype "passive"))
    )
    (net (code "81") (name "Net-(D21-A)") (class "Default")
      (node (ref "12V_IN") (pin "1") (pinfunction "1_1") (pintype "passive"))
      (node (ref "D21") (pin "1") (pinfunction "A_1") (pintype "passive"))
    )
    (net (code "82") (name "Net-(D21-K)") (class "Default")
      (node (ref "D21") (pin "2") (pinfunction "K_2") (pintype "passive"))
      (node (ref "F21") (pin "1") (pinfunction "1_1") (pintype "passive"))
    )
    (net (code "83") (name "Net-(D31-AK)") (class "Default")
      (node (ref "C31") (pin "2") (pinfunction "2_2") (pintype "passive"))
      (node (ref "D31") (pin "3") (pinfunction "AK_3") (pintype "passive"))
      (node (ref "R31") (pin "2") (pinfunction "2_2") (pintype "passive"))
      (node (ref "R34") (pin "2") (pinfunction "2_2") (pintype "passive"))
      (node (ref "R35") (pin "1") (pinfunction "1_1") (pintype "passive"))
    )
    (net (code "84") (name "Net-(D32-AK)") (class "Default")
      (node (ref "C32") (pin "2") (pinfunction "2_2") (pintype "passive"))
      (node (ref "D32") (pin "3") (pinfunction "AK_3") (pintype "passive"))
      (node (ref "R32") (pin "2") (pinfunction "2_2") (pintype "passive"))
      (node (ref "R33") (pin "2") (pinfunction "2_2") (pintype "passive"))
      (node (ref "R36") (pin "1") (pinfunction "1_1") (pintype "passive"))
    )
    (net (code "85") (name "Net-(D41-AK)") (class "Default")
      (node (ref "D41") (pin "3") (pinfunction "AK_3") (pintype "passive"))
      (node (ref "R41") (pin "2") (pinfunction "2_2") (pintype "passive"))
      (node (ref "R43") (pin "2") (pinfunction "2_2") (pintype "passive"))
      (node (ref "R45") (pin "1") (pinfunction "1_1") (pintype "passive"))
    )
    (net (code "86") (name "Net-(D42-AK)") (class "Default")
      (node (ref "D42") (pin "3") (pinfunction "AK_3") (pintype "passive"))
      (node (ref "R42") (pin "2") (pinfunction "2_2") (pintype "passive"))
      (node (ref "R44") (pin "2") (pinfunction "2_2") (pintype "passive"))
      (node (ref "R46") (pin "1") (pinfunction "1_1") (pintype "passive"))
    )
    (net (code "87") (name "Net-(DB31-K)") (class "Default")
      (node (ref "DB31") (pin "1") (pinfunction "K_1") (pintype "passive"))
      (node (ref "R31") (pin "1") (pinfunction "1_1") (pintype "passive"))
    )
    (net (code "88") (name "Net-(DB41-K)") (class "Default")
      (node (ref "DB41") (pin "1") (pinfunction "K_1") (pintype "passive"))
      (node (ref "R41") (pin "1") (pinfunction "1_1") (pintype "passive"))
    )
    (net (code "89") (name "Net-(DB42-K)") (class "Default")
      (node (ref "DB42") (pin "1") (pinfunction "K_1") (pintype "passive"))
      (node (ref "R42") (pin "1") (pinfunction "1_1") (pintype "passive"))
    )
    (net (code "90") (name "Net-(NTC-Pad2)") (class "Default")
      (node (ref "NTC") (pin "2") (pinfunction "2_2") (pintype "passive"))
      (node (ref "R14") (pin "1") (pinfunction "1_1") (pintype "passive"))
      (node (ref "R15") (pin "1") (pinfunction "1_1") (pintype "passive"))
    )
    (net (code "91") (name "Net-(Q11-B)") (class "Default")
      (node (ref "Q11") (pin "1") (pinfunction "B_1") (pintype "passive"))
      (node (ref "R18") (pin "2") (pinfunction "2_2") (pintype "passive"))
    )
    (net (code "92") (name "Net-(Q11-C)") (class "Default")
      (node (ref "GLCD 128x64") (pin "8") (pinfunction "8_8") (pintype "passive"))
      (node (ref "Q11") (pin "2") (pinfunction "C_2") (pintype "passive"))
    )
    (net (code "93") (name "VCC") (class "Default")
      (node (ref "+3V3") (pin "A") (pinfunction "A_A") (pintype "passive"))
      (node (ref "C13") (pin "2") (pinfunction "2_2") (pintype "passive"))
      (node (ref "C14") (pin "2") (pinfunction "2_2") (pintype "passive"))
      (node (ref "C15") (pin "2") (pinfunction "2_2") (pintype "passive"))
      (node (ref "C16") (pin "2") (pinfunction "2_2") (pintype "passive"))
      (node (ref "C18") (pin "2") (pinfunction "2_2") (pintype "passive"))
      (node (ref "F22") (pin "2") (pinfunction "2_2") (pintype "passive"))
      (node (ref "IO_EX_PORT") (pin "5") (pinfunction "5_5") (pintype "passive"))
      (node (ref "R11") (pin "2") (pinfunction "2_2") (pintype "passive"))
      (node (ref "U1") (pin "13") (pinfunction "VDDA_13") (pintype "power_in"))
      (node (ref "U1") (pin "19") (pinfunction "VDD_4_19") (pintype "power_in"))
      (node (ref "U1") (pin "32") (pinfunction "VDD_1_32") (pintype "power_in"))
      (node (ref "U1") (pin "48") (pinfunction "VDD_2_48") (pintype "power_in"))
      (node (ref "U1") (pin "64") (pinfunction "VDD_3_64") (pintype "power_in"))
    )
    (net (code "94") (name "unconnected-(Ether-Pad5)") (class "Default")
      (node (ref "Ether") (pin "5") (pinfunction "5_5") (pintype "passive"))
    )
  )
)
